# XBee_Explorer.net
KiCad netlist of a schematic drawn in EAGLE
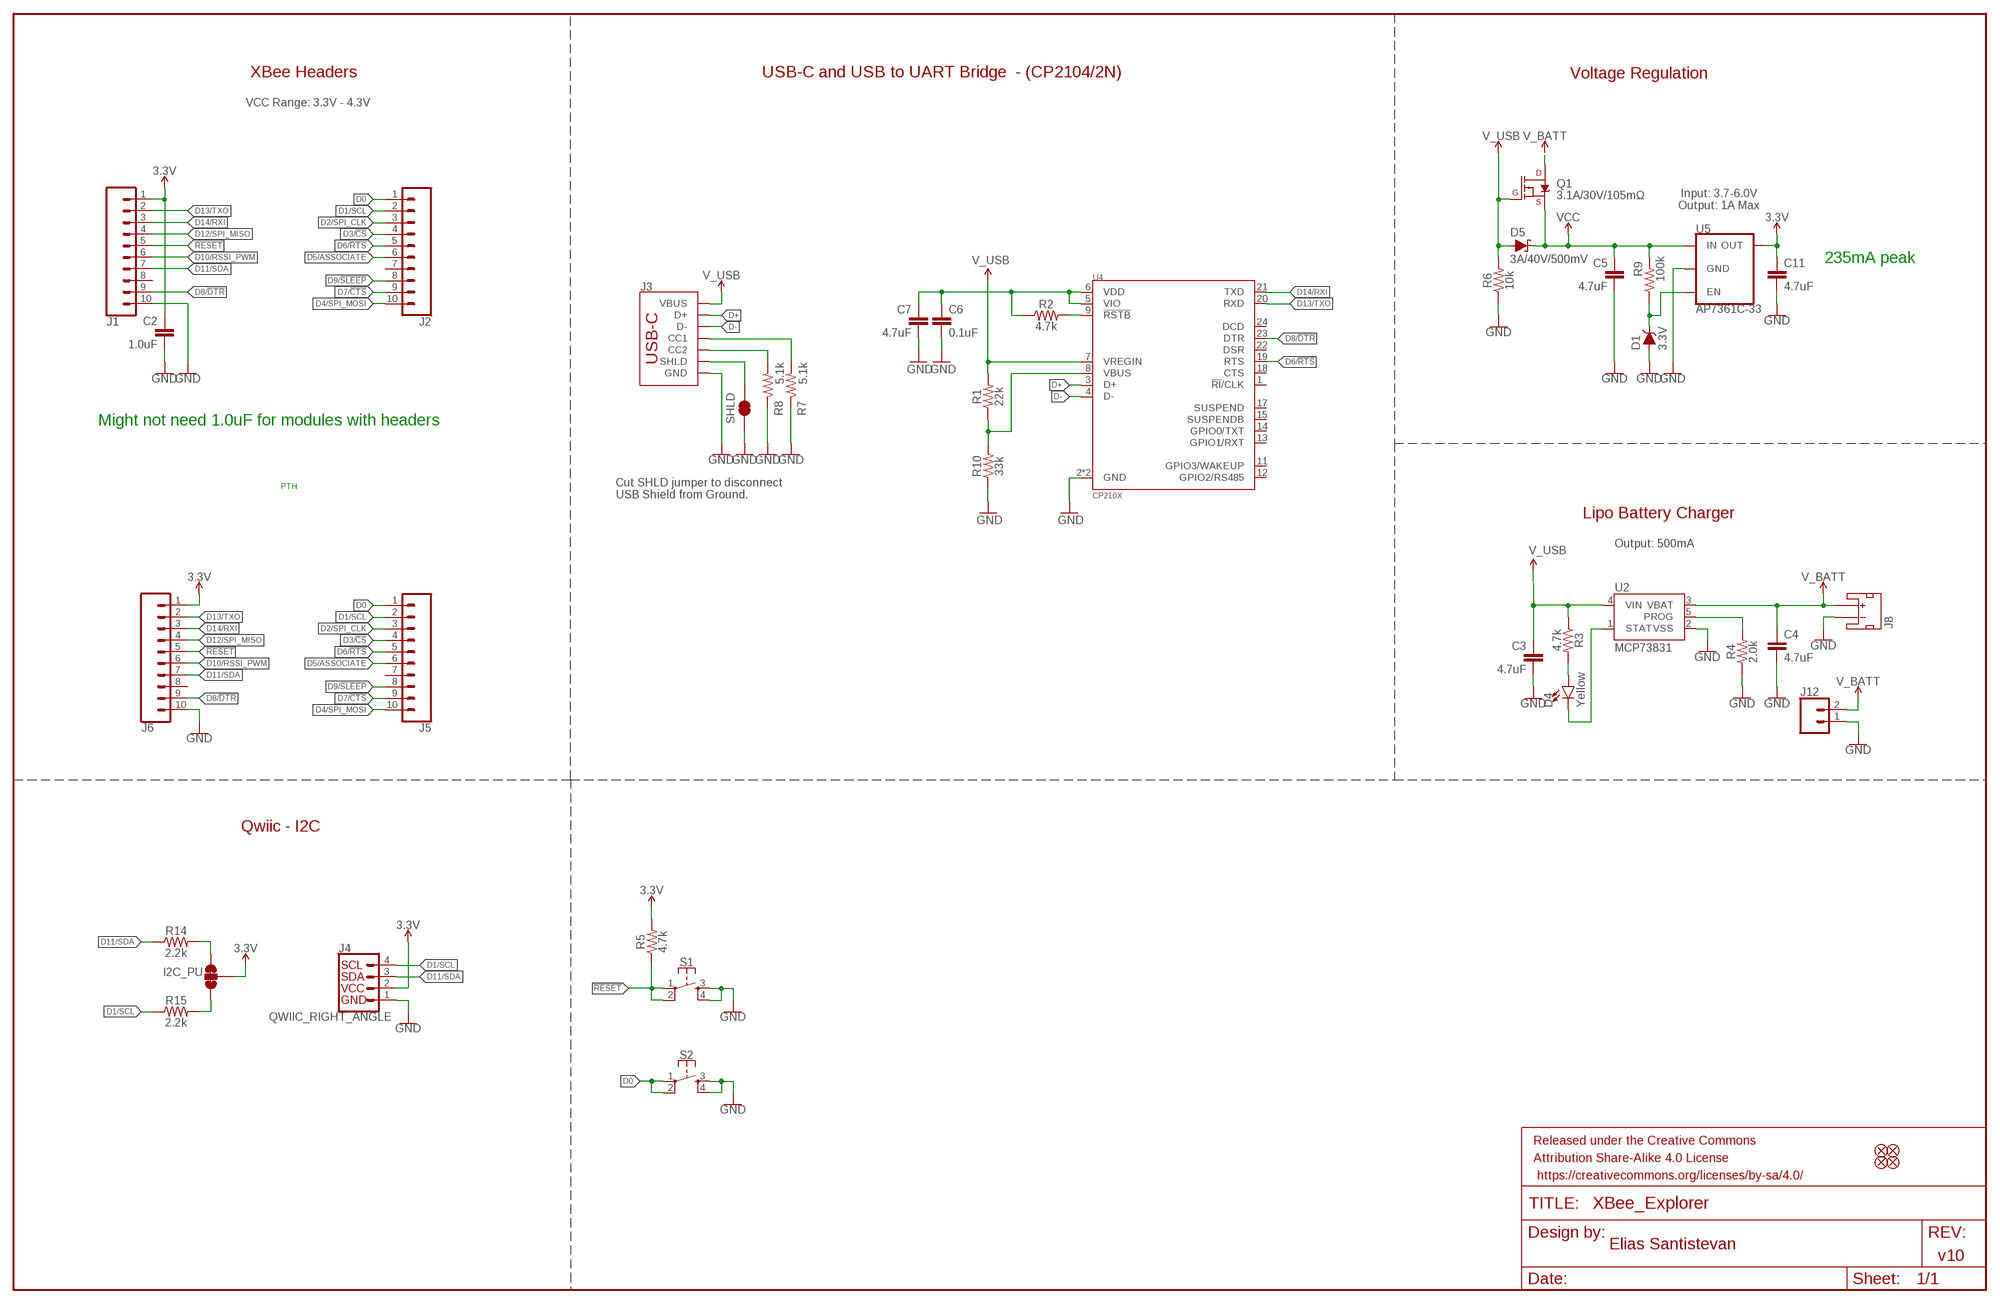
[diagram p0: schematic, sheet 1]

(export (version "E")
  (design (tool "Eeschema 10.0.6"))
  (components
    (comp (ref "C2")
      (value "1.0uF")
      (footprint "eagle-import:0603")
      (libsource (lib "eagle-import") (part "1.0UF-0603-16V-10%"))
    )
    (comp (ref "C3")
      (value "4.7uF")
      (footprint "eagle-import:0603")
      (libsource (lib "eagle-import") (part "4.7UF-0603-6.3V-(10%)"))
    )
    (comp (ref "C4")
      (value "4.7uF")
      (footprint "eagle-import:0603")
      (libsource (lib "eagle-import") (part "4.7UF-0603-35V-(20%)"))
    )
    (comp (ref "C5")
      (value "4.7uF")
      (footprint "eagle-import:0603")
      (libsource (lib "eagle-import") (part "4.7UF-0603-6.3V-(10%)"))
    )
    (comp (ref "C6")
      (value "0.1uF")
      (footprint "eagle-import:0603")
      (libsource (lib "eagle-import") (part "0.1UF-0603-25V-(+80/-20%)"))
    )
    (comp (ref "C7")
      (value "4.7uF")
      (footprint "eagle-import:0603")
      (libsource (lib "eagle-import") (part "4.7UF-0603-6.3V-(10%)"))
    )
    (comp (ref "C11")
      (value "4.7uF")
      (footprint "eagle-import:0603")
      (libsource (lib "eagle-import") (part "4.7UF-0603-6.3V-(10%)"))
    )
    (comp (ref "D1")
      (value "3.3V")
      (footprint "eagle-import:SOD-323")
      (libsource (lib "eagle-import") (part "DIODE-ZENER-MM3Z3V3T1G"))
    )
    (comp (ref "D4")
      (value "Yellow")
      (footprint "eagle-import:LED-0603")
      (libsource (lib "eagle-import") (part "LED-YELLOW0603"))
    )
    (comp (ref "D5")
      (value "3A/40V/500mV")
      (footprint "eagle-import:SMA-DIODE")
      (libsource (lib "eagle-import") (part "DIODE-SCHOTTKY-B340A"))
    )
    (comp (ref "FD1")
      (value "FIDUCIAL1X2")
      (footprint "eagle-import:FIDUCIAL-1X2")
      (libsource (lib "eagle-import") (part "FIDUCIAL1X2"))
    )
    (comp (ref "FD2")
      (value "FIDUCIAL1X2")
      (footprint "eagle-import:FIDUCIAL-1X2")
      (libsource (lib "eagle-import") (part "FIDUCIAL1X2"))
    )
    (comp (ref "FD3")
      (value "FIDUCIAL1X2")
      (footprint "eagle-import:FIDUCIAL-1X2")
      (libsource (lib "eagle-import") (part "FIDUCIAL1X2"))
    )
    (comp (ref "FD4")
      (value "FIDUCIAL1X2")
      (footprint "eagle-import:FIDUCIAL-1X2")
      (libsource (lib "eagle-import") (part "FIDUCIAL1X2"))
    )
    (comp (ref "FRAME1")
      (value "FRAME-LEDGER")
      (footprint "eagle-import:CREATIVE_COMMONS")
      (libsource (lib "eagle-import") (part "FRAME-LEDGER"))
    )
    (comp (ref "I2C_PU")
      (value "JUMPER-SMT_3_2-NC_TRACE_SILK")
      (footprint "eagle-import:SMT-JUMPER_3_2-NC_TRACE_SILK")
      (libsource (lib "eagle-import") (part "JUMPER-SMT_3_2-NC_TRACE_SILK"))
    )
    (comp (ref "J1")
      (value "CONN_10NO_SILK_PTH_FEMALE")
      (footprint "eagle-import:1X10_NO_SILK")
      (libsource (lib "eagle-import") (part "CONN_10NO_SILK_PTH_FEMALE"))
    )
    (comp (ref "J2")
      (value "CONN_10NO_SILK_PTH_FEMALE")
      (footprint "eagle-import:1X10_NO_SILK")
      (libsource (lib "eagle-import") (part "CONN_10NO_SILK_PTH_FEMALE"))
    )
    (comp (ref "J3")
      (value "USB_C_2-LAYER_PADS")
      (footprint "eagle-import:USB-C-16P-2LAYER-PADS")
      (libsource (lib "eagle-import") (part "USB_C_2-LAYER_PADS"))
    )
    (comp (ref "J4")
      (value "QWIIC_RIGHT_ANGLE")
      (footprint "eagle-import:JST04_1MM_RA")
      (libsource (lib "eagle-import") (part "QWIIC_CONNECTORJS-1MM"))
    )
    (comp (ref "J5")
      (value "CONN_10NO_SILK_PTH_FEMALE")
      (footprint "eagle-import:1X10_NO_SILK")
      (libsource (lib "eagle-import") (part "CONN_10NO_SILK_PTH_FEMALE"))
    )
    (comp (ref "J6")
      (value "CONN_10NO_SILK_PTH_FEMALE")
      (footprint "eagle-import:1X10_NO_SILK")
      (libsource (lib "eagle-import") (part "CONN_10NO_SILK_PTH_FEMALE"))
    )
    (comp (ref "J8")
      (value "JST_2MM_MALE")
      (footprint "eagle-import:JST-2-SMD")
      (libsource (lib "eagle-import") (part "JST_2MM_MALE"))
    )
    (comp (ref "J12")
      (value "CONN_021X02_NO_SILK")
      (footprint "eagle-import:1X02_NO_SILK")
      (libsource (lib "eagle-import") (part "CONN_021X02_NO_SILK"))
    )
    (comp (ref "Q1")
      (value "3.1A/30V/105mΩ")
      (footprint "eagle-import:SOT23-3")
      (libsource (lib "eagle-import") (part "MOSFET_PCH-DMG2307L"))
    )
    (comp (ref "R1")
      (value "22k")
      (footprint "eagle-import:0603")
      (libsource (lib "eagle-import") (part "22KOHM-0603-1/10W-1%"))
    )
    (comp (ref "R2")
      (value "4.7k")
      (footprint "eagle-import:0603")
      (libsource (lib "eagle-import") (part "4.7KOHM-0603-1/10W-1%"))
    )
    (comp (ref "R3")
      (value "4.7k")
      (footprint "eagle-import:0603")
      (libsource (lib "eagle-import") (part "4.7KOHM-0603-1/10W-1%"))
    )
    (comp (ref "R4")
      (value "2.0k")
      (footprint "eagle-import:0603")
      (libsource (lib "eagle-import") (part "2.0KOHM-0603-1/10W-5%"))
    )
    (comp (ref "R5")
      (value "4.7k")
      (footprint "eagle-import:0603")
      (libsource (lib "eagle-import") (part "4.7KOHM-0603-1/10W-1%"))
    )
    (comp (ref "R6")
      (value "10k")
      (footprint "eagle-import:0603")
      (libsource (lib "eagle-import") (part "10KOHM-0603-1/10W-1%"))
    )
    (comp (ref "R7")
      (value "5.1k")
      (footprint "eagle-import:0603")
      (libsource (lib "eagle-import") (part "5.1KOHM5.1KOHM-0603-1/10W-1%"))
    )
    (comp (ref "R8")
      (value "5.1k")
      (footprint "eagle-import:0603")
      (libsource (lib "eagle-import") (part "5.1KOHM5.1KOHM-0603-1/10W-1%"))
    )
    (comp (ref "R9")
      (value "100k")
      (footprint "eagle-import:0603")
      (libsource (lib "eagle-import") (part "100KOHM-0603-1/10W-1%"))
    )
    (comp (ref "R10")
      (value "33k")
      (footprint "eagle-import:0603")
      (libsource (lib "eagle-import") (part "33KOHM-0603-1/10W-1%"))
    )
    (comp (ref "R14")
      (value "2.2k")
      (footprint "eagle-import:0603")
      (libsource (lib "eagle-import") (part "2.2KOHM-0603-1/10W-1%"))
    )
    (comp (ref "R15")
      (value "2.2k")
      (footprint "eagle-import:0603")
      (libsource (lib "eagle-import") (part "2.2KOHM-0603-1/10W-1%"))
    )
    (comp (ref "S1")
      (value "MOMENTARY-SWITCH-SPST-2-SMD-5.2MM-TALL")
      (footprint "eagle-import:TACTILE_SWITCH_SMD_5.2MM")
      (libsource (lib "eagle-import") (part "MOMENTARY-SWITCH-SPST-2-SMD-5.2MM-TALL"))
    )
    (comp (ref "S2")
      (value "MOMENTARY-SWITCH-SPST-2-SMD-5.2MM-TALL")
      (footprint "eagle-import:TACTILE_SWITCH_SMD_5.2MM")
      (libsource (lib "eagle-import") (part "MOMENTARY-SWITCH-SPST-2-SMD-5.2MM-TALL"))
    )
    (comp (ref "SHLD")
      (value "JUMPER-SMT_2_NC_TRACE_SILK")
      (footprint "eagle-import:SMT-JUMPER_2_NC_TRACE_SILK")
      (libsource (lib "eagle-import") (part "JUMPER-SMT_2_NC_TRACE_SILK"))
    )
    (comp (ref "U2")
      (value "MCP73831")
      (footprint "eagle-import:SOT23-5")
      (libsource (lib "eagle-import") (part "MCP73831"))
    )
    (comp (ref "U4")
      (value "CP210X")
      (footprint "eagle-import:QFN24")
      (libsource (lib "eagle-import") (part "CP2102N"))
    )
    (comp (ref "U5")
      (value "AP7361C-33")
      (footprint "eagle-import:UDFN-8")
      (libsource (lib "eagle-import") (part "AP7361C-33FGEUDFN-8"))
    )
  )
  (nets
    (net (code "1") (name "/D3{slash}~{CS}") (class "Default")
      (node (ref "J2") (pin "4") (pinfunction "4_4") (pintype "passive"))
      (node (ref "J5") (pin "4") (pinfunction "4_4") (pintype "passive"))
    )
    (net (code "2") (name "/D6{slash}~{RTS}") (class "Default")
      (node (ref "J2") (pin "5") (pinfunction "5_5") (pintype "passive"))
      (node (ref "J5") (pin "5") (pinfunction "5_5") (pintype "passive"))
      (node (ref "U4") (pin "19") (pinfunction "RTS_19") (pintype "bidirectional"))
    )
    (net (code "3") (name "/D7{slash}~{CTS}") (class "Default")
      (node (ref "J2") (pin "9") (pinfunction "9_9") (pintype "passive"))
      (node (ref "J5") (pin "9") (pinfunction "9_9") (pintype "passive"))
    )
    (net (code "4") (name "/D8{slash}~{DTR}") (class "Default")
      (node (ref "J1") (pin "9") (pinfunction "9_9") (pintype "passive"))
      (node (ref "J6") (pin "9") (pinfunction "9_9") (pintype "passive"))
      (node (ref "U4") (pin "23") (pinfunction "DTR_23") (pintype "bidirectional"))
    )
    (net (code "5") (name "/D9{slash}~{SLEEP}") (class "Default")
      (node (ref "J2") (pin "8") (pinfunction "8_8") (pintype "passive"))
      (node (ref "J5") (pin "8") (pinfunction "8_8") (pintype "passive"))
    )
    (net (code "6") (name "/~{RESET}") (class "Default")
      (node (ref "J1") (pin "5") (pinfunction "5_5") (pintype "passive"))
      (node (ref "J6") (pin "5") (pinfunction "5_5") (pintype "passive"))
      (node (ref "R5") (pin "1") (pinfunction "1_1") (pintype "passive"))
      (node (ref "S1") (pin "1") (pinfunction "1_1") (pintype "passive"))
      (node (ref "S1") (pin "2") (pinfunction "2_2") (pintype "passive"))
    )
    (net (code "7") (name "3.3V") (class "Default")
      (node (ref "C11") (pin "1") (pinfunction "1_1") (pintype "passive"))
      (node (ref "C2") (pin "1") (pinfunction "1_1") (pintype "passive"))
      (node (ref "I2C_PU") (pin "2") (pinfunction "2_2") (pintype "passive"))
      (node (ref "J1") (pin "1") (pinfunction "1_1") (pintype "passive"))
      (node (ref "J4") (pin "2") (pinfunction "2_2") (pintype "power_in"))
      (node (ref "J6") (pin "1") (pinfunction "1_1") (pintype "passive"))
      (node (ref "R5") (pin "2") (pinfunction "2_2") (pintype "passive"))
      (node (ref "U5") (pin "1") (pinfunction "OUT_1") (pintype "output"))
    )
    (net (code "8") (name "D+") (class "Default")
      (node (ref "J3") (pin "A6") (pinfunction "D+_A6") (pintype "bidirectional"))
      (node (ref "J3") (pin "B6") (pinfunction "D+_B6") (pintype "bidirectional"))
      (node (ref "U4") (pin "3") (pinfunction "D+_3") (pintype "bidirectional"))
    )
    (net (code "9") (name "D-") (class "Default")
      (node (ref "J3") (pin "A7") (pinfunction "D-_A7") (pintype "bidirectional"))
      (node (ref "J3") (pin "B7") (pinfunction "D-_B7") (pintype "bidirectional"))
      (node (ref "U4") (pin "4") (pinfunction "D-_4") (pintype "bidirectional"))
    )
    (net (code "10") (name "D0") (class "Default")
      (node (ref "J2") (pin "1") (pinfunction "1_1") (pintype "passive"))
      (node (ref "J5") (pin "1") (pinfunction "1_1") (pintype "passive"))
      (node (ref "S2") (pin "1") (pinfunction "1_1") (pintype "passive"))
      (node (ref "S2") (pin "2") (pinfunction "2_2") (pintype "passive"))
    )
    (net (code "11") (name "D1{slash}SCL") (class "Default")
      (node (ref "J2") (pin "2") (pinfunction "2_2") (pintype "passive"))
      (node (ref "J4") (pin "4") (pinfunction "4_4") (pintype "passive"))
      (node (ref "J5") (pin "2") (pinfunction "2_2") (pintype "passive"))
      (node (ref "R15") (pin "1") (pinfunction "1_1") (pintype "passive"))
    )
    (net (code "12") (name "D2{slash}SPI_CLK") (class "Default")
      (node (ref "J2") (pin "3") (pinfunction "3_3") (pintype "passive"))
      (node (ref "J5") (pin "3") (pinfunction "3_3") (pintype "passive"))
    )
    (net (code "13") (name "D4{slash}SPI_MOSI") (class "Default")
      (node (ref "J2") (pin "10") (pinfunction "10_10") (pintype "passive"))
      (node (ref "J5") (pin "10") (pinfunction "10_10") (pintype "passive"))
    )
    (net (code "14") (name "D5{slash}ASSOCIATE") (class "Default")
      (node (ref "J2") (pin "6") (pinfunction "6_6") (pintype "passive"))
      (node (ref "J5") (pin "6") (pinfunction "6_6") (pintype "passive"))
    )
    (net (code "15") (name "D10{slash}RSSI_PWM") (class "Default")
      (node (ref "J1") (pin "6") (pinfunction "6_6") (pintype "passive"))
      (node (ref "J6") (pin "6") (pinfunction "6_6") (pintype "passive"))
    )
    (net (code "16") (name "D11{slash}SDA") (class "Default")
      (node (ref "J1") (pin "7") (pinfunction "7_7") (pintype "passive"))
      (node (ref "J4") (pin "3") (pinfunction "3_3") (pintype "passive"))
      (node (ref "J6") (pin "7") (pinfunction "7_7") (pintype "passive"))
      (node (ref "R14") (pin "1") (pinfunction "1_1") (pintype "passive"))
    )
    (net (code "17") (name "D12{slash}SPI_MISO") (class "Default")
      (node (ref "J1") (pin "4") (pinfunction "4_4") (pintype "passive"))
      (node (ref "J6") (pin "4") (pinfunction "4_4") (pintype "passive"))
    )
    (net (code "18") (name "D13{slash}TXO") (class "Default")
      (node (ref "J1") (pin "2") (pinfunction "2_2") (pintype "passive"))
      (node (ref "J6") (pin "2") (pinfunction "2_2") (pintype "passive"))
      (node (ref "U4") (pin "20") (pinfunction "RXD_20") (pintype "bidirectional"))
    )
    (net (code "19") (name "D14{slash}RXI") (class "Default")
      (node (ref "J1") (pin "3") (pinfunction "3_3") (pintype "passive"))
      (node (ref "J6") (pin "3") (pinfunction "3_3") (pintype "passive"))
      (node (ref "U4") (pin "21") (pinfunction "TXD_21") (pintype "bidirectional"))
    )
    (net (code "20") (name "GND") (class "Default")
      (node (ref "C11") (pin "2") (pinfunction "2_2") (pintype "passive"))
      (node (ref "C2") (pin "2") (pinfunction "2_2") (pintype "passive"))
      (node (ref "C3") (pin "2") (pinfunction "2_2") (pintype "passive"))
      (node (ref "C4") (pin "2") (pinfunction "2_2") (pintype "passive"))
      (node (ref "C5") (pin "2") (pinfunction "2_2") (pintype "passive"))
      (node (ref "C6") (pin "2") (pinfunction "2_2") (pintype "passive"))
      (node (ref "C7") (pin "2") (pinfunction "2_2") (pintype "passive"))
      (node (ref "D1") (pin "A") (pinfunction "A_A") (pintype "passive"))
      (node (ref "J1") (pin "10") (pinfunction "10_10") (pintype "passive"))
      (node (ref "J12") (pin "1") (pinfunction "1_1") (pintype "passive"))
      (node (ref "J3") (pin "GND") (pinfunction "GND_GND") (pintype "bidirectional"))
      (node (ref "J3") (pin "GND2") (pinfunction "GND_GND2") (pintype "bidirectional"))
      (node (ref "J4") (pin "1") (pinfunction "1_1") (pintype "power_in"))
      (node (ref "J6") (pin "10") (pinfunction "10_10") (pintype "passive"))
      (node (ref "J8") (pin "1") (pinfunction "-_1") (pintype "bidirectional"))
      (node (ref "R10") (pin "1") (pinfunction "1_1") (pintype "passive"))
      (node (ref "R4") (pin "1") (pinfunction "1_1") (pintype "passive"))
      (node (ref "R6") (pin "1") (pinfunction "1_1") (pintype "passive"))
      (node (ref "R7") (pin "1") (pinfunction "1_1") (pintype "passive"))
      (node (ref "R8") (pin "1") (pinfunction "1_1") (pintype "passive"))
      (node (ref "S1") (pin "3") (pinfunction "3_3") (pintype "passive"))
      (node (ref "S1") (pin "4") (pinfunction "4_4") (pintype "passive"))
      (node (ref "S2") (pin "3") (pinfunction "3_3") (pintype "passive"))
      (node (ref "S2") (pin "4") (pinfunction "4_4") (pintype "passive"))
      (node (ref "SHLD") (pin "1") (pinfunction "1_1") (pintype "passive"))
      (node (ref "U2") (pin "2") (pinfunction "VSS_2") (pintype "power_in"))
      (node (ref "U4") (pin "2") (pinfunction "GND_2") (pintype "bidirectional"))
      (node (ref "U4") (pin "PAD") (pinfunction "GND_PAD") (pintype "bidirectional"))
      (node (ref "U5") (pin "4") (pinfunction "GND_4") (pintype "input"))
      (node (ref "U5") (pin "EP") (pinfunction "GND_EP") (pintype "input"))
    )
    (net (code "21") (name "Net-(D4-PadA)") (class "Default")
      (node (ref "D4") (pin "A") (pinfunction "A_A") (pintype "passive"))
      (node (ref "R3") (pin "2") (pinfunction "2_2") (pintype "passive"))
    )
    (net (code "22") (name "Net-(I2C_PU-Pad1)") (class "Default")
      (node (ref "I2C_PU") (pin "1") (pinfunction "1_1") (pintype "passive"))
      (node (ref "R15") (pin "2") (pinfunction "2_2") (pintype "passive"))
    )
    (net (code "23") (name "Net-(I2C_PU-Pad3)") (class "Default")
      (node (ref "I2C_PU") (pin "3") (pinfunction "3_3") (pintype "passive"))
      (node (ref "R14") (pin "2") (pinfunction "2_2") (pintype "passive"))
    )
    (net (code "24") (name "Net-(J3-CC1)") (class "Default")
      (node (ref "J3") (pin "A5") (pinfunction "CC1_A5") (pintype "bidirectional"))
      (node (ref "R7") (pin "2") (pinfunction "2_2") (pintype "passive"))
    )
    (net (code "25") (name "Net-(J3-CC2)") (class "Default")
      (node (ref "J3") (pin "B5") (pinfunction "CC2_B5") (pintype "bidirectional"))
      (node (ref "R8") (pin "2") (pinfunction "2_2") (pintype "passive"))
    )
    (net (code "26") (name "Net-(J3-SHLD-PadSHLD1)") (class "Default")
      (node (ref "J3") (pin "SHLD1") (pinfunction "SHLD_SHLD1") (pintype "bidirectional"))
      (node (ref "J3") (pin "SHLD2") (pinfunction "SHLD_SHLD2") (pintype "bidirectional"))
      (node (ref "J3") (pin "SHLD3") (pinfunction "SHLD_SHLD3") (pintype "bidirectional"))
      (node (ref "J3") (pin "SHLD4") (pinfunction "SHLD_SHLD4") (pintype "bidirectional"))
      (node (ref "SHLD") (pin "2") (pinfunction "2_2") (pintype "passive"))
    )
    (net (code "27") (name "Net-(U2-PROG)") (class "Default")
      (node (ref "R4") (pin "2") (pinfunction "2_2") (pintype "passive"))
      (node (ref "U2") (pin "5") (pinfunction "PROG_5") (pintype "input"))
    )
    (net (code "28") (name "Net-(U2-STAT)") (class "Default")
      (node (ref "D4") (pin "C") (pinfunction "C_C") (pintype "passive"))
      (node (ref "U2") (pin "1") (pinfunction "STAT_1") (pintype "output"))
    )
    (net (code "29") (name "Net-(U2-VIN)") (class "Default")
      (node (ref "C3") (pin "1") (pinfunction "1_1") (pintype "passive"))
      (node (ref "R3") (pin "1") (pinfunction "1_1") (pintype "passive"))
      (node (ref "U2") (pin "4") (pinfunction "VIN_4") (pintype "power_in"))
    )
    (net (code "30") (name "Net-(U4-VBUS)") (class "Default")
      (node (ref "R1") (pin "1") (pinfunction "1_1") (pintype "passive"))
      (node (ref "R10") (pin "2") (pinfunction "2_2") (pintype "passive"))
      (node (ref "U4") (pin "8") (pinfunction "VBUS_8") (pintype "bidirectional"))
    )
    (net (code "31") (name "Net-(U4-VDD)") (class "Default")
      (node (ref "C6") (pin "1") (pinfunction "1_1") (pintype "passive"))
      (node (ref "C7") (pin "1") (pinfunction "1_1") (pintype "passive"))
      (node (ref "R2") (pin "1") (pinfunction "1_1") (pintype "passive"))
      (node (ref "U4") (pin "5") (pinfunction "VIO_5") (pintype "bidirectional"))
      (node (ref "U4") (pin "6") (pinfunction "VDD_6") (pintype "bidirectional"))
    )
    (net (code "32") (name "Net-(U4-~{RSTB})") (class "Default")
      (node (ref "R2") (pin "2") (pinfunction "2_2") (pintype "passive"))
      (node (ref "U4") (pin "9") (pinfunction "~{RSTB}_9") (pintype "bidirectional"))
    )
    (net (code "33") (name "Net-(U5-EN)") (class "Default")
      (node (ref "D1") (pin "C") (pinfunction "C_C") (pintype "passive"))
      (node (ref "R9") (pin "1") (pinfunction "1_1") (pintype "passive"))
      (node (ref "U5") (pin "5") (pinfunction "EN_5") (pintype "bidirectional"))
    )
    (net (code "34") (name "VCC") (class "Default")
      (node (ref "C5") (pin "1") (pinfunction "1_1") (pintype "passive"))
      (node (ref "D5") (pin "C") (pinfunction "C_C") (pintype "passive"))
      (node (ref "Q1") (pin "2") (pinfunction "S_2") (pintype "bidirectional"))
      (node (ref "R9") (pin "2") (pinfunction "2_2") (pintype "passive"))
      (node (ref "U5") (pin "8") (pinfunction "IN_8") (pintype "input"))
    )
    (net (code "35") (name "V_BATT") (class "Default")
      (node (ref "C4") (pin "1") (pinfunction "1_1") (pintype "passive"))
      (node (ref "J12") (pin "2") (pinfunction "2_2") (pintype "passive"))
      (node (ref "J8") (pin "2") (pinfunction "+_2") (pintype "bidirectional"))
      (node (ref "Q1") (pin "3") (pinfunction "D_3") (pintype "bidirectional"))
      (node (ref "U2") (pin "3") (pinfunction "VBAT_3") (pintype "power_in"))
    )
    (net (code "36") (name "V_USB") (class "Default")
      (node (ref "D5") (pin "A") (pinfunction "A_A") (pintype "passive"))
      (node (ref "J3") (pin "VBUS1") (pinfunction "VBUS_VBUS1") (pintype "bidirectional"))
      (node (ref "J3") (pin "VBUS2") (pinfunction "VBUS_VBUS2") (pintype "bidirectional"))
      (node (ref "Q1") (pin "1") (pinfunction "G_1") (pintype "bidirectional"))
      (node (ref "R1") (pin "2") (pinfunction "2_2") (pintype "passive"))
      (node (ref "R6") (pin "2") (pinfunction "2_2") (pintype "passive"))
      (node (ref "U4") (pin "7") (pinfunction "VREGIN_7") (pintype "bidirectional"))
    )
    (net (code "37") (name "unconnected-(J1-Pad8)") (class "Default")
      (node (ref "J1") (pin "8") (pinfunction "8_8") (pintype "passive"))
    )
    (net (code "38") (name "unconnected-(J2-Pad7)") (class "Default")
      (node (ref "J2") (pin "7") (pinfunction "7_7") (pintype "passive"))
    )
    (net (code "39") (name "unconnected-(J5-Pad7)") (class "Default")
      (node (ref "J5") (pin "7") (pinfunction "7_7") (pintype "passive"))
    )
    (net (code "40") (name "unconnected-(J6-Pad8)") (class "Default")
      (node (ref "J6") (pin "8") (pinfunction "8_8") (pintype "passive"))
    )
    (net (code "41") (name "unconnected-(J8-PAD1-PadNC1)") (class "Default")
      (node (ref "J8") (pin "NC1") (pinfunction "PAD1_NC1") (pintype "bidirectional"))
    )
    (net (code "42") (name "unconnected-(J8-PAD2-PadNC2)") (class "Default")
      (node (ref "J8") (pin "NC2") (pinfunction "PAD2_NC2") (pintype "bidirectional"))
    )
    (net (code "43") (name "unconnected-(U4-CTS-Pad18)") (class "Default")
      (node (ref "U4") (pin "18") (pinfunction "CTS_18") (pintype "bidirectional"))
    )
    (net (code "44") (name "unconnected-(U4-DCD-Pad24)") (class "Default")
      (node (ref "U4") (pin "24") (pinfunction "DCD_24") (pintype "bidirectional"))
    )
    (net (code "45") (name "unconnected-(U4-DSR-Pad22)") (class "Default")
      (node (ref "U4") (pin "22") (pinfunction "DSR_22") (pintype "bidirectional"))
    )
    (net (code "46") (name "unconnected-(U4-GPIO0{slash}TXT-Pad14)") (class "Default")
      (node (ref "U4") (pin "14") (pinfunction "GPIO0/TXT_14") (pintype "bidirectional"))
    )
    (net (code "47") (name "unconnected-(U4-GPIO1{slash}RXT-Pad13)") (class "Default")
      (node (ref "U4") (pin "13") (pinfunction "GPIO1/RXT_13") (pintype "bidirectional"))
    )
    (net (code "48") (name "unconnected-(U4-GPIO2{slash}RS485-Pad12)") (class "Default")
      (node (ref "U4") (pin "12") (pinfunction "GPIO2/RS485_12") (pintype "bidirectional"))
    )
    (net (code "49") (name "unconnected-(U4-GPIO3{slash}WAKEUP-Pad11)") (class "Default")
      (node (ref "U4") (pin "11") (pinfunction "GPIO3/WAKEUP_11") (pintype "bidirectional"))
    )
    (net (code "50") (name "unconnected-(U4-SUSPEND-Pad17)") (class "Default")
      (node (ref "U4") (pin "17") (pinfunction "SUSPEND_17") (pintype "bidirectional"))
    )
    (net (code "51") (name "unconnected-(U4-SUSPENDB-Pad15)") (class "Default")
      (node (ref "U4") (pin "15") (pinfunction "SUSPENDB_15") (pintype "bidirectional"))
    )
    (net (code "52") (name "unconnected-(U4-~{RI}{slash}CLK-Pad1)") (class "Default")
      (node (ref "U4") (pin "1") (pinfunction "~{RI}/CLK_1") (pintype "bidirectional"))
    )
  )
)
